# MCU.net
KiCad netlist of a schematic drawn in Altium Designer
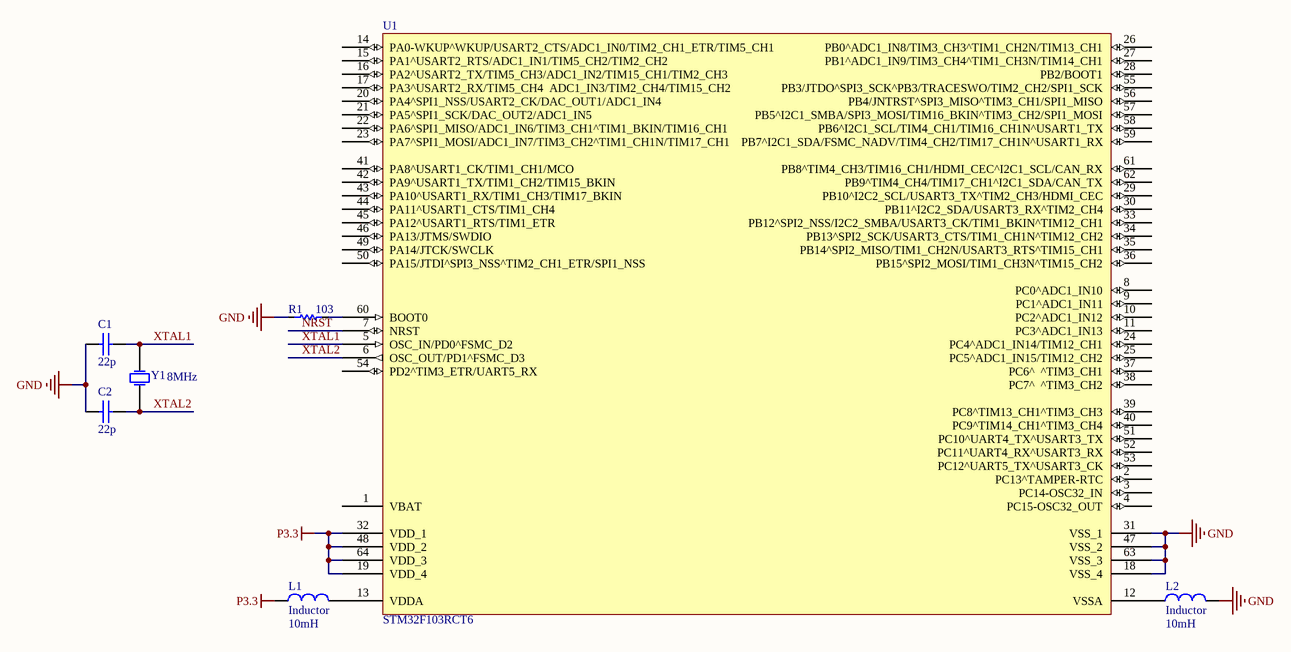
[diagram p0: MCU.SchDoc]

(export (version "E")
  (design (tool "Eeschema 10.0.6"))
  (components
    (comp (ref "C1")
      (value "22p")
      (footprint "CAP_SMD_0805")
      (description "Non-polarized Capacitor")
      (fields (field (name "Comment") "Cap Non-pol") (field (name "PUBLISHER") "Altium Limited"))
      (libsource (lib "jmctvs") (part "Cap Non-pol"))
    )
    (comp (ref "C2")
      (value "22p")
      (footprint "CAP_SMD_0805")
      (description "Non-polarized Capacitor")
      (fields (field (name "Comment") "Cap Non-pol") (field (name "PUBLISHER") "Altium Limited"))
      (libsource (lib "jmctvs") (part "Cap Non-pol"))
    )
    (comp (ref "L1")
      (value "Inductor")
      (footprint "L-0805")
      (fields (field (name "ALTIUM_VALUE") "10mH") (field (name "PUBLISHER") "Altium Limited"))
      (libsource (lib "jmctvs") (part "Inductor"))
    )
    (comp (ref "L2")
      (value "Inductor")
      (footprint "L-0805")
      (fields (field (name "ALTIUM_VALUE") "10mH") (field (name "PUBLISHER") "Altium Limited"))
      (libsource (lib "jmctvs") (part "Inductor"))
    )
    (comp (ref "R1")
      (value "103")
      (footprint "RES_SMD_0805")
      (description "Resistor")
      (fields (field (name "Comment") "RESISTOR") (field (name "PUBLISHER") "Altium Limited"))
      (libsource (lib "jmctvs") (part "RESISTOR"))
    )
    (comp (ref "U1")
      (value "STM32F103RCT6")
      (footprint "jmctvs:TQFP64L")
      (description "MCU 32-bit STM32F1 ARM Cortex M3 RISC 64KB Flash 2.5V/3.3V 64-Pin LQFP Tray")
      (libsource (lib "jmctvs") (part "STM32F103RCT6"))
    )
    (comp (ref "Y1")
      (value "8MHz")
      (footprint "XTAL")
      (description "Crystal Oscillator")
      (fields (field (name "PUBLISHER") "Altium Limited"))
      (libsource (lib "jmctvs") (part "XTAL"))
    )
  )
  (nets
    (net (code "1") (name "/NRST") (class "Default")
      (node (ref "U1") (pin "7") (pinfunction "NRST_7") (pintype "bidirectional"))
    )
    (net (code "2") (name "/XTAL1") (class "Default")
      (node (ref "C1") (pin "2") (pinfunction "2_2") (pintype "passive"))
      (node (ref "U1") (pin "5") (pinfunction "OSC_IN/PD0^FSMC_D2_5") (pintype "input"))
      (node (ref "Y1") (pin "2") (pinfunction "OSC2_2") (pintype "passive"))
    )
    (net (code "3") (name "/XTAL2") (class "Default")
      (node (ref "C2") (pin "2") (pinfunction "2_2") (pintype "passive"))
      (node (ref "U1") (pin "6") (pinfunction "OSC_OUT/PD1^FSMC_D3_6") (pintype "output"))
      (node (ref "Y1") (pin "1") (pinfunction "OSC1_1") (pintype "passive"))
    )
    (net (code "4") (name "GND") (class "Default")
      (node (ref "C1") (pin "1") (pinfunction "1_1") (pintype "passive"))
      (node (ref "C2") (pin "1") (pinfunction "1_1") (pintype "passive"))
      (node (ref "L2") (pin "2") (pinfunction "2_2") (pintype "passive"))
      (node (ref "R1") (pin "1") (pinfunction "1_1") (pintype "passive"))
      (node (ref "U1") (pin "18") (pinfunction "VSS_4_18") (pintype "power_in"))
      (node (ref "U1") (pin "31") (pinfunction "VSS_1_31") (pintype "power_in"))
      (node (ref "U1") (pin "47") (pinfunction "VSS_2_47") (pintype "power_in"))
      (node (ref "U1") (pin "63") (pinfunction "VSS_3_63") (pintype "power_in"))
    )
    (net (code "5") (name "Net-(U1-BOOT0)") (class "Default")
      (node (ref "R1") (pin "2") (pinfunction "2_2") (pintype "passive"))
      (node (ref "U1") (pin "60") (pinfunction "BOOT0_60") (pintype "input"))
    )
    (net (code "6") (name "Net-(U1-VDDA)") (class "Default")
      (node (ref "L1") (pin "2") (pinfunction "2_2") (pintype "passive"))
      (node (ref "U1") (pin "13") (pinfunction "VDDA_13") (pintype "power_in"))
    )
    (net (code "7") (name "Net-(U1-VSSA)") (class "Default")
      (node (ref "L2") (pin "1") (pinfunction "1_1") (pintype "passive"))
      (node (ref "U1") (pin "12") (pinfunction "VSSA_12") (pintype "power_in"))
    )
    (net (code "8") (name "P3.3") (class "Default")
      (node (ref "L1") (pin "1") (pinfunction "1_1") (pintype "passive"))
      (node (ref "U1") (pin "19") (pinfunction "VDD_4_19") (pintype "power_in"))
      (node (ref "U1") (pin "32") (pinfunction "VDD_1_32") (pintype "power_in"))
      (node (ref "U1") (pin "48") (pinfunction "VDD_2_48") (pintype "power_in"))
      (node (ref "U1") (pin "64") (pinfunction "VDD_3_64") (pintype "power_in"))
    )
    (net (code "9") (name "unconnected-(U1-PA0-WKUP^WKUP{slash}USART2_CTS{slash}ADC1_IN0{slash}TIM2_CH1_ETR{slash}TIM5_CH1-Pad14)") (class "Default")
      (node (ref "U1") (pin "14") (pinfunction "PA0-WKUP^WKUP/USART2_CTS/ADC1_IN0/TIM2_CH1_ETR/TIM5_CH1_14") (pintype "bidirectional"))
    )
    (net (code "10") (name "unconnected-(U1-PA1^USART2_RTS{slash}ADC1_IN1{slash}TIM5_CH2{slash}TIM2_CH2-Pad15)") (class "Default")
      (node (ref "U1") (pin "15") (pinfunction "PA1^USART2_RTS/ADC1_IN1/TIM5_CH2/TIM2_CH2_15") (pintype "bidirectional"))
    )
    (net (code "11") (name "unconnected-(U1-PA2^USART2_TX{slash}TIM5_CH3{slash}ADC1_IN2{slash}TIM15_CH1{slash}TIM2_CH3-Pad16)") (class "Default")
      (node (ref "U1") (pin "16") (pinfunction "PA2^USART2_TX/TIM5_CH3/ADC1_IN2/TIM15_CH1/TIM2_CH3_16") (pintype "bidirectional"))
    )
    (net (code "12") (name "unconnected-(U1-PA3^USART2_RX{slash}TIM5_CH4__ADC1_IN3{slash}TIM2_CH4{slash}TIM15_CH2-Pad17)") (class "Default")
      (node (ref "U1") (pin "17") (pinfunction "PA3^USART2_RX/TIM5_CH4__ADC1_IN3/TIM2_CH4/TIM15_CH2_17") (pintype "bidirectional"))
    )
    (net (code "13") (name "unconnected-(U1-PA4^SPI1_NSS{slash}USART2_CK{slash}DAC_OUT1{slash}ADC1_IN4-Pad20)") (class "Default")
      (node (ref "U1") (pin "20") (pinfunction "PA4^SPI1_NSS/USART2_CK/DAC_OUT1/ADC1_IN4_20") (pintype "bidirectional"))
    )
    (net (code "14") (name "unconnected-(U1-PA5^SPI1_SCK{slash}DAC_OUT2{slash}ADC1_IN5-Pad21)") (class "Default")
      (node (ref "U1") (pin "21") (pinfunction "PA5^SPI1_SCK/DAC_OUT2/ADC1_IN5_21") (pintype "bidirectional"))
    )
    (net (code "15") (name "unconnected-(U1-PA6^SPI1_MISO{slash}ADC1_IN6{slash}TIM3_CH1^TIM1_BKIN{slash}TIM16_CH1-Pad22)") (class "Default")
      (node (ref "U1") (pin "22") (pinfunction "PA6^SPI1_MISO/ADC1_IN6/TIM3_CH1^TIM1_BKIN/TIM16_CH1_22") (pintype "bidirectional"))
    )
    (net (code "16") (name "unconnected-(U1-PA7^SPI1_MOSI{slash}ADC1_IN7{slash}TIM3_CH2^TIM1_CH1N{slash}TIM17_CH1-Pad23)") (class "Default")
      (node (ref "U1") (pin "23") (pinfunction "PA7^SPI1_MOSI/ADC1_IN7/TIM3_CH2^TIM1_CH1N/TIM17_CH1_23") (pintype "bidirectional"))
    )
    (net (code "17") (name "unconnected-(U1-PA8^USART1_CK{slash}TIM1_CH1{slash}MCO-Pad41)") (class "Default")
      (node (ref "U1") (pin "41") (pinfunction "PA8^USART1_CK/TIM1_CH1/MCO_41") (pintype "bidirectional"))
    )
    (net (code "18") (name "unconnected-(U1-PA9^USART1_TX{slash}TIM1_CH2{slash}TIM15_BKIN-Pad42)") (class "Default")
      (node (ref "U1") (pin "42") (pinfunction "PA9^USART1_TX/TIM1_CH2/TIM15_BKIN_42") (pintype "bidirectional"))
    )
    (net (code "19") (name "unconnected-(U1-PA10^USART1_RX{slash}TIM1_CH3{slash}TIM17_BKIN-Pad43)") (class "Default")
      (node (ref "U1") (pin "43") (pinfunction "PA10^USART1_RX/TIM1_CH3/TIM17_BKIN_43") (pintype "bidirectional"))
    )
    (net (code "20") (name "unconnected-(U1-PA11^USART1_CTS{slash}TIM1_CH4-Pad44)") (class "Default")
      (node (ref "U1") (pin "44") (pinfunction "PA11^USART1_CTS/TIM1_CH4_44") (pintype "bidirectional"))
    )
    (net (code "21") (name "unconnected-(U1-PA12^USART1_RTS{slash}TIM1_ETR-Pad45)") (class "Default")
      (node (ref "U1") (pin "45") (pinfunction "PA12^USART1_RTS/TIM1_ETR_45") (pintype "bidirectional"))
    )
    (net (code "22") (name "unconnected-(U1-PA13{slash}JTMS{slash}SWDIO-Pad46)") (class "Default")
      (node (ref "U1") (pin "46") (pinfunction "PA13/JTMS/SWDIO_46") (pintype "bidirectional"))
    )
    (net (code "23") (name "unconnected-(U1-PA14{slash}JTCK{slash}SWCLK-Pad49)") (class "Default")
      (node (ref "U1") (pin "49") (pinfunction "PA14/JTCK/SWCLK_49") (pintype "bidirectional"))
    )
    (net (code "24") (name "unconnected-(U1-PA15{slash}JTDI^SPI3_NSS^TIM2_CH1_ETR{slash}SPI1_NSS-Pad50)") (class "Default")
      (node (ref "U1") (pin "50") (pinfunction "PA15/JTDI^SPI3_NSS^TIM2_CH1_ETR/SPI1_NSS_50") (pintype "bidirectional"))
    )
    (net (code "25") (name "unconnected-(U1-PB0^ADC1_IN8{slash}TIM3_CH3^TIM1_CH2N{slash}TIM13_CH1-Pad26)") (class "Default")
      (node (ref "U1") (pin "26") (pinfunction "PB0^ADC1_IN8/TIM3_CH3^TIM1_CH2N/TIM13_CH1_26") (pintype "bidirectional"))
    )
    (net (code "26") (name "unconnected-(U1-PB1^ADC1_IN9{slash}TIM3_CH4^TIM1_CH3N{slash}TIM14_CH1-Pad27)") (class "Default")
      (node (ref "U1") (pin "27") (pinfunction "PB1^ADC1_IN9/TIM3_CH4^TIM1_CH3N/TIM14_CH1_27") (pintype "bidirectional"))
    )
    (net (code "27") (name "unconnected-(U1-PB2{slash}BOOT1-Pad28)") (class "Default")
      (node (ref "U1") (pin "28") (pinfunction "PB2/BOOT1_28") (pintype "bidirectional"))
    )
    (net (code "28") (name "unconnected-(U1-PB3{slash}JTDO^SPI3_SCK^PB3{slash}TRACESWO{slash}TIM2_CH2{slash}SPI1_SCK-Pad55)") (class "Default")
      (node (ref "U1") (pin "55") (pinfunction "PB3/JTDO^SPI3_SCK^PB3/TRACESWO/TIM2_CH2/SPI1_SCK_55") (pintype "bidirectional"))
    )
    (net (code "29") (name "unconnected-(U1-PB4{slash}JNTRST^SPI3_MISO^TIM3_CH1{slash}SPI1_MISO-Pad56)") (class "Default")
      (node (ref "U1") (pin "56") (pinfunction "PB4/JNTRST^SPI3_MISO^TIM3_CH1/SPI1_MISO_56") (pintype "bidirectional"))
    )
    (net (code "30") (name "unconnected-(U1-PB5^I2C1_SMBA{slash}SPI3_MOSI{slash}TIM16_BKIN^TIM3_CH2{slash}SPI1_MOSI-Pad57)") (class "Default")
      (node (ref "U1") (pin "57") (pinfunction "PB5^I2C1_SMBA/SPI3_MOSI/TIM16_BKIN^TIM3_CH2/SPI1_MOSI_57") (pintype "bidirectional"))
    )
    (net (code "31") (name "unconnected-(U1-PB6^I2C1_SCL{slash}TIM4_CH1{slash}TIM16_CH1N^USART1_TX-Pad58)") (class "Default")
      (node (ref "U1") (pin "58") (pinfunction "PB6^I2C1_SCL/TIM4_CH1/TIM16_CH1N^USART1_TX_58") (pintype "bidirectional"))
    )
    (net (code "32") (name "unconnected-(U1-PB7^I2C1_SDA{slash}FSMC_NADV{slash}TIM4_CH2{slash}TIM17_CH1N^USART1_RX-Pad59)") (class "Default")
      (node (ref "U1") (pin "59") (pinfunction "PB7^I2C1_SDA/FSMC_NADV/TIM4_CH2/TIM17_CH1N^USART1_RX_59") (pintype "bidirectional"))
    )
    (net (code "33") (name "unconnected-(U1-PB8^TIM4_CH3{slash}TIM16_CH1{slash}HDMI_CEC^I2C1_SCL{slash}CAN_RX-Pad61)") (class "Default")
      (node (ref "U1") (pin "61") (pinfunction "PB8^TIM4_CH3/TIM16_CH1/HDMI_CEC^I2C1_SCL/CAN_RX_61") (pintype "bidirectional"))
    )
    (net (code "34") (name "unconnected-(U1-PB9^TIM4_CH4{slash}TIM17_CH1^I2C1_SDA{slash}CAN_TX-Pad62)") (class "Default")
      (node (ref "U1") (pin "62") (pinfunction "PB9^TIM4_CH4/TIM17_CH1^I2C1_SDA/CAN_TX_62") (pintype "bidirectional"))
    )
    (net (code "35") (name "unconnected-(U1-PB10^I2C2_SCL{slash}USART3_TX^TIM2_CH3{slash}HDMI_CEC-Pad29)") (class "Default")
      (node (ref "U1") (pin "29") (pinfunction "PB10^I2C2_SCL/USART3_TX^TIM2_CH3/HDMI_CEC_29") (pintype "bidirectional"))
    )
    (net (code "36") (name "unconnected-(U1-PB11^I2C2_SDA{slash}USART3_RX^TIM2_CH4-Pad30)") (class "Default")
      (node (ref "U1") (pin "30") (pinfunction "PB11^I2C2_SDA/USART3_RX^TIM2_CH4_30") (pintype "bidirectional"))
    )
    (net (code "37") (name "unconnected-(U1-PB12^SPI2_NSS{slash}I2C2_SMBA{slash}USART3_CK{slash}TIM1_BKIN^TIM12_CH1-Pad33)") (class "Default")
      (node (ref "U1") (pin "33") (pinfunction "PB12^SPI2_NSS/I2C2_SMBA/USART3_CK/TIM1_BKIN^TIM12_CH1_33") (pintype "bidirectional"))
    )
    (net (code "38") (name "unconnected-(U1-PB13^SPI2_SCK{slash}USART3_CTS{slash}TIM1_CH1N^TIM12_CH2-Pad34)") (class "Default")
      (node (ref "U1") (pin "34") (pinfunction "PB13^SPI2_SCK/USART3_CTS/TIM1_CH1N^TIM12_CH2_34") (pintype "bidirectional"))
    )
    (net (code "39") (name "unconnected-(U1-PB14^SPI2_MISO{slash}TIM1_CH2N{slash}USART3_RTS^TIM15_CH1-Pad35)") (class "Default")
      (node (ref "U1") (pin "35") (pinfunction "PB14^SPI2_MISO/TIM1_CH2N/USART3_RTS^TIM15_CH1_35") (pintype "bidirectional"))
    )
    (net (code "40") (name "unconnected-(U1-PB15^SPI2_MOSI{slash}TIM1_CH3N^TIM15_CH2-Pad36)") (class "Default")
      (node (ref "U1") (pin "36") (pinfunction "PB15^SPI2_MOSI/TIM1_CH3N^TIM15_CH2_36") (pintype "bidirectional"))
    )
    (net (code "41") (name "unconnected-(U1-PC0^ADC1_IN10-Pad8)") (class "Default")
      (node (ref "U1") (pin "8") (pinfunction "PC0^ADC1_IN10_8") (pintype "bidirectional"))
    )
    (net (code "42") (name "unconnected-(U1-PC1^ADC1_IN11-Pad9)") (class "Default")
      (node (ref "U1") (pin "9") (pinfunction "PC1^ADC1_IN11_9") (pintype "bidirectional"))
    )
    (net (code "43") (name "unconnected-(U1-PC2^ADC1_IN12-Pad10)") (class "Default")
      (node (ref "U1") (pin "10") (pinfunction "PC2^ADC1_IN12_10") (pintype "bidirectional"))
    )
    (net (code "44") (name "unconnected-(U1-PC3^ADC1_IN13-Pad11)") (class "Default")
      (node (ref "U1") (pin "11") (pinfunction "PC3^ADC1_IN13_11") (pintype "bidirectional"))
    )
    (net (code "45") (name "unconnected-(U1-PC4^ADC1_IN14{slash}TIM12_CH1-Pad24)") (class "Default")
      (node (ref "U1") (pin "24") (pinfunction "PC4^ADC1_IN14/TIM12_CH1_24") (pintype "bidirectional"))
    )
    (net (code "46") (name "unconnected-(U1-PC5^ADC1_IN15{slash}TIM12_CH2-Pad25)") (class "Default")
      (node (ref "U1") (pin "25") (pinfunction "PC5^ADC1_IN15/TIM12_CH2_25") (pintype "bidirectional"))
    )
    (net (code "47") (name "unconnected-(U1-PC6^__^TIM3_CH1-Pad37)") (class "Default")
      (node (ref "U1") (pin "37") (pinfunction "PC6^__^TIM3_CH1_37") (pintype "bidirectional"))
    )
    (net (code "48") (name "unconnected-(U1-PC7^__^TIM3_CH2-Pad38)") (class "Default")
      (node (ref "U1") (pin "38") (pinfunction "PC7^__^TIM3_CH2_38") (pintype "bidirectional"))
    )
    (net (code "49") (name "unconnected-(U1-PC8^TIM13_CH1^TIM3_CH3-Pad39)") (class "Default")
      (node (ref "U1") (pin "39") (pinfunction "PC8^TIM13_CH1^TIM3_CH3_39") (pintype "bidirectional"))
    )
    (net (code "50") (name "unconnected-(U1-PC9^TIM14_CH1^TIM3_CH4-Pad40)") (class "Default")
      (node (ref "U1") (pin "40") (pinfunction "PC9^TIM14_CH1^TIM3_CH4_40") (pintype "bidirectional"))
    )
    (net (code "51") (name "unconnected-(U1-PC10^UART4_TX^USART3_TX-Pad51)") (class "Default")
      (node (ref "U1") (pin "51") (pinfunction "PC10^UART4_TX^USART3_TX_51") (pintype "bidirectional"))
    )
    (net (code "52") (name "unconnected-(U1-PC11^UART4_RX^USART3_RX-Pad52)") (class "Default")
      (node (ref "U1") (pin "52") (pinfunction "PC11^UART4_RX^USART3_RX_52") (pintype "bidirectional"))
    )
    (net (code "53") (name "unconnected-(U1-PC12^UART5_TX^USART3_CK-Pad53)") (class "Default")
      (node (ref "U1") (pin "53") (pinfunction "PC12^UART5_TX^USART3_CK_53") (pintype "bidirectional"))
    )
    (net (code "54") (name "unconnected-(U1-PC13^TAMPER-RTC-Pad2)") (class "Default")
      (node (ref "U1") (pin "2") (pinfunction "PC13^TAMPER-RTC_2") (pintype "bidirectional"))
    )
    (net (code "55") (name "unconnected-(U1-PC14-OSC32_IN-Pad3)") (class "Default")
      (node (ref "U1") (pin "3") (pinfunction "PC14-OSC32_IN_3") (pintype "bidirectional"))
    )
    (net (code "56") (name "unconnected-(U1-PC15-OSC32_OUT-Pad4)") (class "Default")
      (node (ref "U1") (pin "4") (pinfunction "PC15-OSC32_OUT_4") (pintype "bidirectional"))
    )
    (net (code "57") (name "unconnected-(U1-PD2^TIM3_ETR{slash}UART5_RX-Pad54)") (class "Default")
      (node (ref "U1") (pin "54") (pinfunction "PD2^TIM3_ETR/UART5_RX_54") (pintype "bidirectional"))
    )
    (net (code "58") (name "unconnected-(U1-VBAT-Pad1)") (class "Default")
      (node (ref "U1") (pin "1") (pinfunction "VBAT_1") (pintype "power_in"))
    )
  )
)
